# Flash.net
KiCad netlist of a schematic drawn in Altium Designer
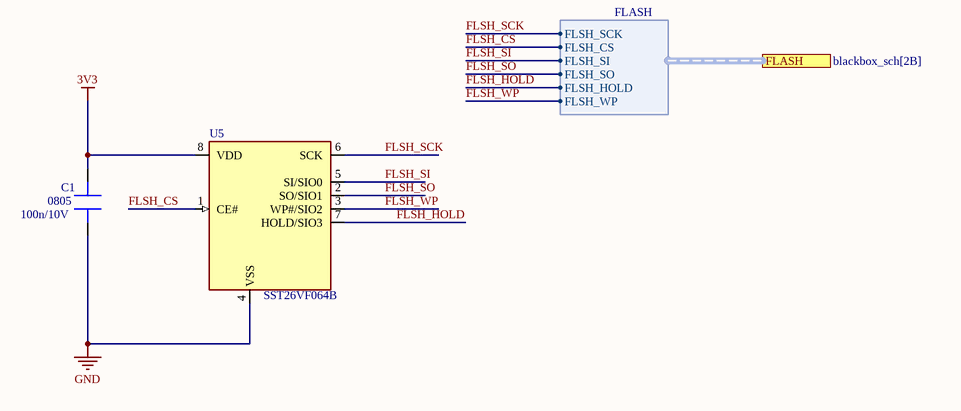
[diagram p0: Flash.SchDoc]

(export (version "E")
  (design (tool "Eeschema 10.0.6"))
  (components
    (comp (ref "C1")
      (value "100n/10V")
      (footprint "CAPC2012X09L [0805]")
      (description "Standard capacitor")
      (fields (field (name "PACKAGE") "0805") (field (name "Comment") "C"))
      (libsource (lib "SR_Library") (part "C"))
    )
    (comp (ref "U5")
      (value "SST26VF064B/BA")
      (footprint "SON127P500X80-8N_T")
      (description "64 Mbit Serial Quad I/O (SQI) Flash Memory, 2V5/3V")
      (fields (field (name "PN") "SST26VF064B"))
      (libsource (lib "_IC_Memory") (part "SST26VF064B/BA"))
    )
  )
  (nets
    (net (code "2") (name "/FLSH_CS") (class "Default")
      (node (ref "U5") (pin "1") (pinfunction "CE#_1") (pintype "input"))
    )
    (net (code "3") (name "/FLSH_HOLD") (class "Default")
      (node (ref "U5") (pin "7") (pinfunction "HOLD/SIO3_7") (pintype "bidirectional"))
    )
    (net (code "4") (name "/FLSH_SCK") (class "Default")
      (node (ref "U5") (pin "6") (pinfunction "SCK_6") (pintype "bidirectional"))
    )
    (net (code "5") (name "/FLSH_SI") (class "Default")
      (node (ref "U5") (pin "5") (pinfunction "SI/SIO0_5") (pintype "bidirectional"))
    )
    (net (code "6") (name "/FLSH_SO") (class "Default")
      (node (ref "U5") (pin "2") (pinfunction "SO/SIO1_2") (pintype "bidirectional"))
    )
    (net (code "7") (name "/FLSH_WP") (class "Default")
      (node (ref "U5") (pin "3") (pinfunction "WP#/SIO2_3") (pintype "bidirectional"))
    )
    (net (code "9") (name "3V3") (class "Default")
      (node (ref "C1") (pin "2") (pinfunction "2_2") (pintype "passive"))
      (node (ref "U5") (pin "8") (pinfunction "VDD_8") (pintype "power_in"))
    )
    (net (code "10") (name "GND") (class "Default")
      (node (ref "C1") (pin "1") (pinfunction "1_1") (pintype "passive"))
      (node (ref "U5") (pin "4") (pinfunction "VSS_4") (pintype "power_in"))
    )
  )
)
